# Main.net
KiCad netlist of a schematic drawn in Altium Designer
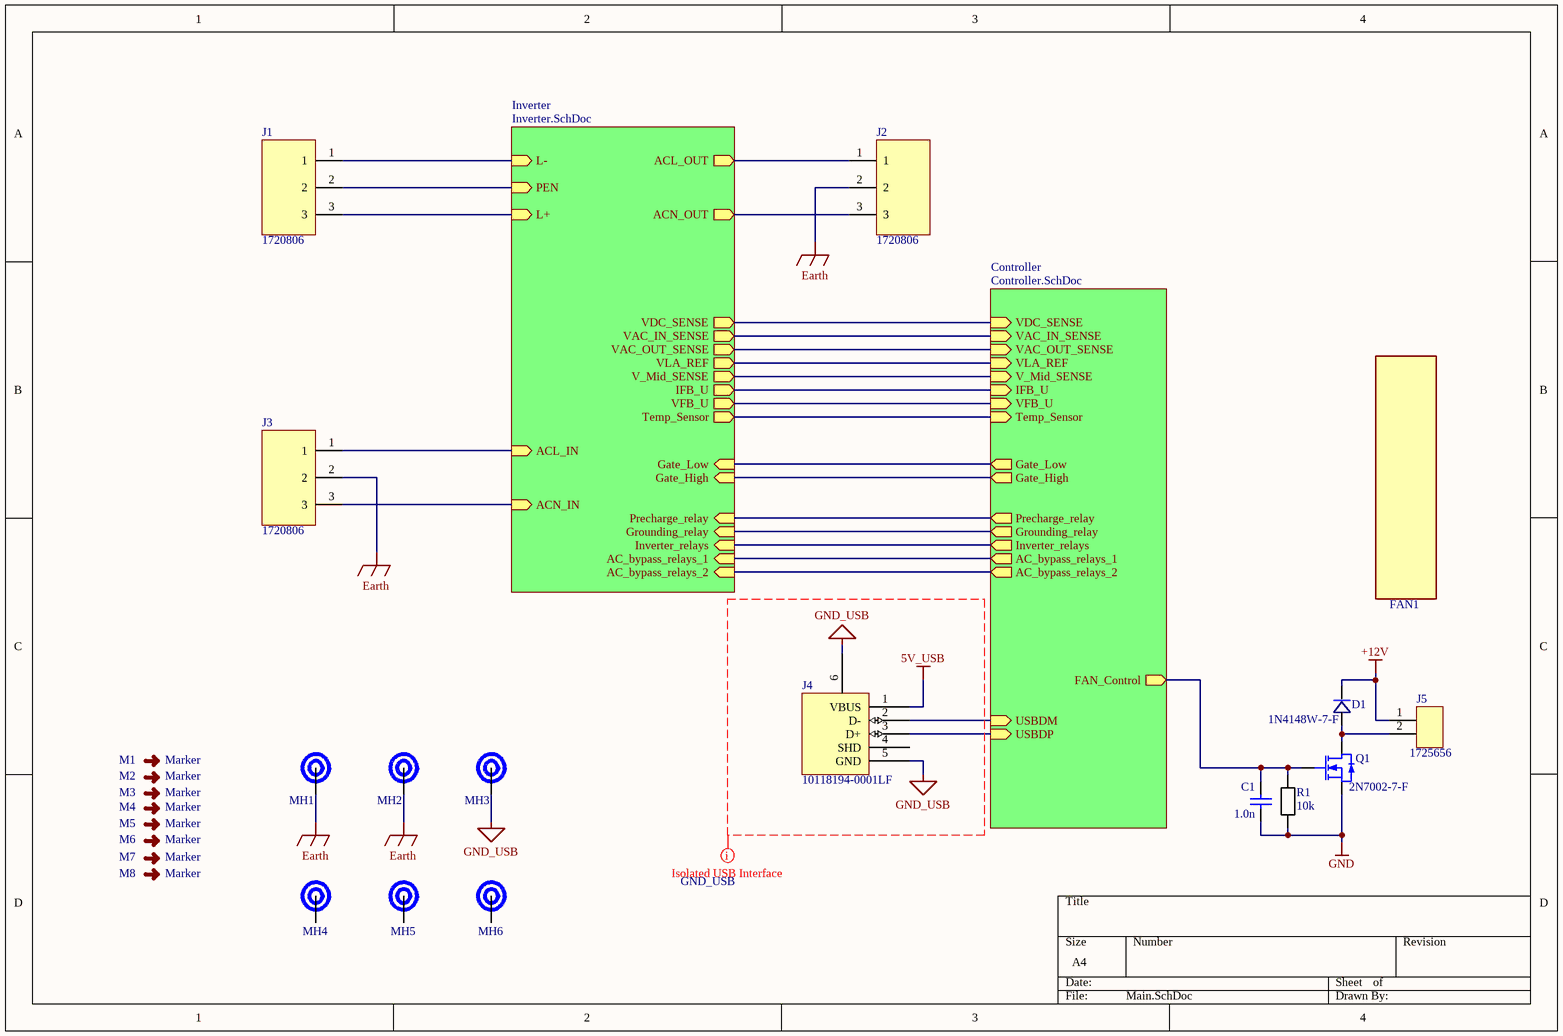
[diagram p0: Main.SchDoc]

(export (version "E")
  (design (tool "Eeschema 10.0.6"))
  (components
    (comp (ref "C1")
      (value "1.0n")
      (footprint "C0603")
      (description "Capacitor 1.0n 0603 +-10% 50V")
      (fields (field (name "PART NUMBER") "CAP_YAG_CC0603KRNPO9BN102_NPO") (field (name "MFR") "Yageo"))
      (libsource (lib "Cap_Yag_0603_NPO_50_10%$") (part "CAP_YAG_CC0603KRNPO9BN102_NPO"))
    )
    (comp (ref "D1")
      (value "1N4148W-7-F")
      (footprint "SOD123")
      (description "Diodes - General Purpose, Power, Switching SURFACE MOUNT FAST SWITCHING DIODE")
      (fields (field (name "MFR") "Diodes Incorporated"))
      (libsource (lib "EnergyMeter") (part "1N4148W"))
    )
    (comp (ref "FAN1")
      (value "FAN_60*60mm")
      (footprint "FAN_60*60mm")
      (libsource (lib "Inverter_2kW") (part "FAN_60*60mm"))
    )
    (comp (ref "J1")
      (value "1720806")
      (footprint "1720806")
      (description "Pluggable Terminal Blocks 3 Pos 7.62mm pitch Through Hole Header")
      (fields (field (name "MFR") "Phoenix Contact"))
      (libsource (lib "") (part "1720806_1"))
    )
    (comp (ref "J2")
      (value "1720806")
      (footprint "1720806")
      (description "Pluggable Terminal Blocks 3 Pos 7.62mm pitch Through Hole Header")
      (fields (field (name "MFR") "Phoenix Contact"))
      (libsource (lib "Inverter_2kW") (part "1720806"))
    )
    (comp (ref "J3")
      (value "1720806")
      (footprint "1720806")
      (description "Pluggable Terminal Blocks 3 Pos 7.62mm pitch Through Hole Header")
      (fields (field (name "MFR") "Phoenix Contact"))
      (libsource (lib "") (part "1720806_1"))
    )
    (comp (ref "J4")
      (value "10118194-0001LF")
      (footprint "10118194-0001LF")
      (description "CONN RCPT USB2.0 MICRO B SMD R/A")
      (fields (field (name "MFR") "Amphenol FCI"))
      (libsource (lib "LED_LIB") (part "10118194-0001LF"))
    )
    (comp (ref "J5")
      (value "1725656")
      (footprint "1725656")
      (description "Fixed Terminal Blocks 2P 2.54mm 90DEG")
      (fields (field (name "MFR") "Phoenix Contact"))
      (libsource (lib "Charger") (part "Connector_2Pin"))
    )
    (comp (ref "M1") (value "Marker") (footprint "PASSER-KREIS") (libsource (lib "*") (part "M")))
    (comp (ref "M2") (value "Marker") (footprint "PASSER-KREIS") (libsource (lib "*") (part "M")))
    (comp (ref "M3") (value "Marker") (footprint "PASSER-KREIS") (libsource (lib "*") (part "M")))
    (comp (ref "M4") (value "Marker") (footprint "PASSER-KREIS") (libsource (lib "*") (part "M")))
    (comp (ref "M5") (value "Marker") (footprint "PASSER-KREIS") (libsource (lib "*") (part "M")))
    (comp (ref "M6") (value "Marker") (footprint "PASSER-KREIS") (libsource (lib "*") (part "M")))
    (comp (ref "M7") (value "Marker") (footprint "PASSER-KREIS") (libsource (lib "*") (part "M")))
    (comp (ref "M8") (value "Marker") (footprint "PASSER-KREIS") (libsource (lib "*") (part "M")))
    (comp (ref "MH1")
      (value "No Fit")
      (footprint "MountingHole")
      (libsource (lib "Inverter_2kW") (part "Mounting Hole"))
    )
    (comp (ref "MH2")
      (value "No Fit")
      (footprint "MountingHole")
      (libsource (lib "Inverter_2kW") (part "Mounting Hole"))
    )
    (comp (ref "MH3")
      (value "No Fit")
      (footprint "MountingHole")
      (libsource (lib "Inverter_2kW") (part "Mounting Hole"))
    )
    (comp (ref "MH4")
      (value "No Fit")
      (footprint "MountingHole_Cutout")
      (libsource (lib "Inverter_2kW") (part "Mounting Hole"))
    )
    (comp (ref "MH5")
      (value "No Fit")
      (footprint "MountingHole_Cutout")
      (libsource (lib "Inverter_2kW") (part "Mounting Hole"))
    )
    (comp (ref "MH6")
      (value "No Fit")
      (footprint "MountingHole_Cutout")
      (libsource (lib "Inverter_2kW") (part "Mounting Hole"))
    )
    (comp (ref "Q1")
      (value "2N7002-7-F")
      (footprint "SOT23-3N")
      (description "MOSFET N-CH 60V 200MA SOT23-3")
      (fields (field (name "MFR") "Diodes Incorporated"))
      (libsource (lib "BidirectionalCharger") (part "MOSFET-N"))
    )
    (comp (ref "R1")
      (value "10k")
      (footprint "R0603")
      (description "0.1W/ 10kohm±1%")
      (fields (field (name "MPN") "RC0603FR-0710KL") (field (name "MFR") "Yageo"))
      (libsource (lib "RCL") (part "RES"))
    )
  )
  (nets
    (net (code "1") (name "+12V") (class "Default")
      (node (ref "D1") (pin "C") (pinfunction "C_C") (pintype "passive"))
      (node (ref "J5") (pin "1") (pinfunction "1_1") (pintype "passive"))
    )
    (net (code "2") (name "/ACL_IN") (class "Default")
      (node (ref "J3") (pin "1") (pinfunction "1_1") (pintype "passive"))
    )
    (net (code "3") (name "/ACL_OUT") (class "Default")
      (node (ref "J2") (pin "1") (pinfunction "1_1") (pintype "passive"))
    )
    (net (code "4") (name "/ACN_IN") (class "Default")
      (node (ref "J3") (pin "3") (pinfunction "3_3") (pintype "passive"))
    )
    (net (code "5") (name "/ACN_OUT") (class "Default")
      (node (ref "J2") (pin "3") (pinfunction "3_3") (pintype "passive"))
    )
    (net (code "8") (name "/FAN_Control") (class "Default")
      (node (ref "C1") (pin "2") (pinfunction "2_2") (pintype "passive"))
      (node (ref "Q1") (pin "1") (pinfunction "G_1") (pintype "passive"))
      (node (ref "R1") (pin "1") (pinfunction "1_1") (pintype "passive"))
    )
    (net (code "14") (name "/L+") (class "Default")
      (node (ref "J1") (pin "3") (pinfunction "3_3") (pintype "passive"))
    )
    (net (code "15") (name "/L-") (class "Default")
      (node (ref "J1") (pin "1") (pinfunction "1_1") (pintype "passive"))
    )
    (net (code "16") (name "/PEN") (class "Default")
      (node (ref "J1") (pin "2") (pinfunction "2_2") (pintype "passive"))
    )
    (net (code "19") (name "/USBDM") (class "Default")
      (node (ref "J4") (pin "2") (pinfunction "D-_2") (pintype "bidirectional"))
    )
    (net (code "20") (name "/USBDP") (class "Default")
      (node (ref "J4") (pin "3") (pinfunction "D+_3") (pintype "bidirectional"))
    )
    (net (code "27") (name "5V_USB") (class "Default")
      (node (ref "J4") (pin "1") (pinfunction "VBUS_1") (pintype "power_in"))
    )
    (net (code "28") (name "Earth") (class "Default")
      (node (ref "J2") (pin "2") (pinfunction "2_2") (pintype "passive"))
      (node (ref "J3") (pin "2") (pinfunction "2_2") (pintype "passive"))
      (node (ref "MH1") (pin "0") (pinfunction "0_0") (pintype "passive"))
      (node (ref "MH2") (pin "0") (pinfunction "0_0") (pintype "passive"))
    )
    (net (code "29") (name "GND") (class "Default")
      (node (ref "C1") (pin "1") (pinfunction "1_1") (pintype "passive"))
      (node (ref "Q1") (pin "2") (pinfunction "S_2") (pintype "passive"))
      (node (ref "R1") (pin "2") (pinfunction "2_2") (pintype "passive"))
    )
    (net (code "30") (name "GND_USB") (class "Default")
      (node (ref "J4") (pin "5") (pinfunction "GND_5") (pintype "power_in"))
      (node (ref "J4") (pin "6") (pintype "passive"))
      (node (ref "MH3") (pin "0") (pinfunction "0_0") (pintype "passive"))
    )
    (net (code "31") (name "Net-(Q1-D)") (class "Default")
      (node (ref "D1") (pin "A") (pinfunction "A_A") (pintype "passive"))
      (node (ref "J5") (pin "2") (pinfunction "2_2") (pintype "passive"))
      (node (ref "Q1") (pin "3") (pinfunction "D_3") (pintype "passive"))
    )
    (net (code "32") (name "unconnected-(J4-SHD-Pad4)") (class "Default")
      (node (ref "J4") (pin "4") (pinfunction "SHD_4") (pintype "passive"))
    )
    (net (code "33") (name "unconnected-(MH4-Pad0)") (class "Default")
      (node (ref "MH4") (pin "0") (pinfunction "0_0") (pintype "passive"))
    )
    (net (code "34") (name "unconnected-(MH5-Pad0)") (class "Default")
      (node (ref "MH5") (pin "0") (pinfunction "0_0") (pintype "passive"))
    )
    (net (code "35") (name "unconnected-(MH6-Pad0)") (class "Default")
      (node (ref "MH6") (pin "0") (pinfunction "0_0") (pintype "passive"))
    )
  )
)
